# P4_CCD_CAM_BOARD_MCU.net
KiCad netlist of a schematic drawn in Altium Designer
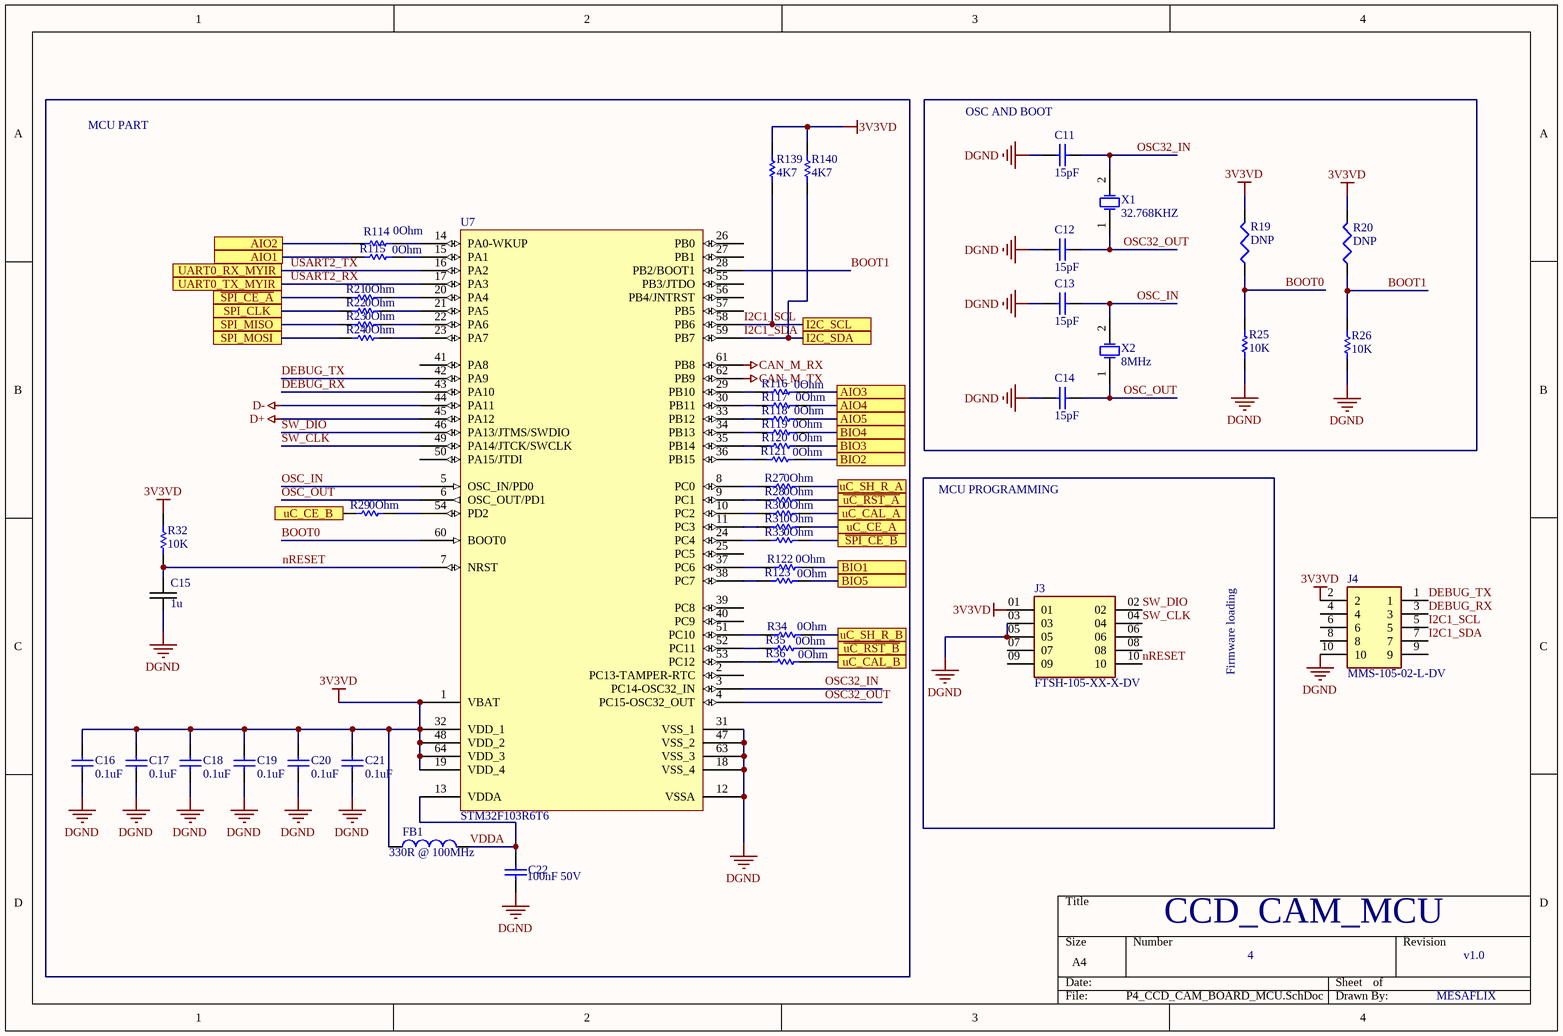
[diagram p0: P4_CCD_CAM_BOARD_MCU.SchDoc]

(export (version "E")
  (design (tool "Eeschema 10.0.6"))
  (components
    (comp (ref "C11")
      (value "15pF")
      (footprint "CAP0603")
      (description "CAP CER 15PF 50V C0G/NP0 0603")
      (libsource (lib "CAP_Library") (part "CAP0603_15pF"))
    )
    (comp (ref "C12")
      (value "15pF")
      (footprint "CAP0603")
      (description "CAP CER 15PF 50V C0G/NP0 0603")
      (libsource (lib "CAP_Library") (part "CAP0603_15pF"))
    )
    (comp (ref "C13")
      (value "15pF")
      (footprint "CAP0603")
      (description "CAP CER 15PF 50V C0G/NP0 0603")
      (libsource (lib "CAP_Library") (part "CAP0603_15pF"))
    )
    (comp (ref "C14")
      (value "15pF")
      (footprint "CAP0603")
      (description "CAP CER 15PF 50V C0G/NP0 0603")
      (libsource (lib "CAP_Library") (part "CAP0603_15pF"))
    )
    (comp (ref "C15")
      (value "1u")
      (footprint "C0603")
      (description "CAP CER 1UF 25V X7R 0603")
      (fields
        (field (name "MANUFACTURER PART NUMBER") "CL10B105KA8NNNC")
        (field (name "DIGIKEY PART NUMBER") "1276-1184-1-ND")
      )
      (libsource (lib "Database_Lib") (part "Capacitor"))
    )
    (comp (ref "C16")
      (value "0.1uF")
      (footprint "C 0402(1005)x0.5")
      (description "Capacitor")
      (fields
        (field (name "MANUFACTURER") "Murata")
        (field (name "MANUFACTURER PART NUMBER") "GRM155R71C104KA88D")
      )
      (libsource (lib "Miscellaneous Devices") (part "Cap"))
    )
    (comp (ref "C17")
      (value "0.1uF")
      (footprint "C 0402(1005)x0.5")
      (description "Capacitor")
      (fields
        (field (name "MANUFACTURER") "Murata")
        (field (name "MANUFACTURER PART NUMBER") "GRM155R71C104KA88D")
      )
      (libsource (lib "Miscellaneous Devices") (part "Cap"))
    )
    (comp (ref "C18")
      (value "0.1uF")
      (footprint "C 0402(1005)x0.5")
      (description "Capacitor")
      (fields
        (field (name "MANUFACTURER") "Murata")
        (field (name "MANUFACTURER PART NUMBER") "GRM155R71C104KA88D")
      )
      (libsource (lib "Miscellaneous Devices") (part "Cap"))
    )
    (comp (ref "C19")
      (value "0.1uF")
      (footprint "C 0402(1005)x0.5")
      (description "Capacitor")
      (fields
        (field (name "MANUFACTURER") "Murata")
        (field (name "MANUFACTURER PART NUMBER") "GRM155R71C104KA88D")
      )
      (libsource (lib "Miscellaneous Devices") (part "Cap"))
    )
    (comp (ref "C20")
      (value "0.1uF")
      (footprint "C 0402(1005)x0.5")
      (description "Capacitor")
      (fields
        (field (name "MANUFACTURER") "Murata")
        (field (name "MANUFACTURER PART NUMBER") "GRM155R71C104KA88D")
      )
      (libsource (lib "Miscellaneous Devices") (part "Cap"))
    )
    (comp (ref "C21")
      (value "0.1uF")
      (footprint "C 0402(1005)x0.5")
      (description "Capacitor")
      (fields
        (field (name "MANUFACTURER") "Murata")
        (field (name "MANUFACTURER PART NUMBER") "GRM155R71C104KA88D")
      )
      (libsource (lib "Miscellaneous Devices") (part "Cap"))
    )
    (comp (ref "C22")
      (value "100nF 50V")
      (footprint "CAP0603")
      (description "CAP CER 0.1UF 50V X7R 0603")
      (libsource (lib "CAP_Library") (part "CAP0603_100nF"))
    )
    (comp (ref "FB1")
      (value "330R @ 100MHz")
      (footprint "FB0603")
      (description "FERRITE BEAD 330 OHM 0603 1LN")
      (libsource (lib "FB_Library") (part "FB0603_330R@100MHz"))
    )
    (comp (ref "J3")
      (value "FTSH-105-XX-X-DV")
      (footprint "SAMTEC_FTSH-105-XX-X-DV")
      (description "Connector Header Surface Mount 10 position 0.050 (1.27mm)")
      (fields (field (name "MF") "Samtec") (field (name "MP") "FTSH-105-01-L-DV"))
      (libsource (lib "FTSH-105-XX-X-DV") (part "FTSH-105-XX-X-DV"))
    )
    (comp (ref "J4")
      (value "MMS-105-02-L-DV")
      (footprint "SAMTEC_MMS-105-02-L-DV")
      (description "10 Position Receptacle Connector Surface Mount")
      (fields (field (name "MF") "Samtec"))
      (libsource (lib "CCD_CAM_BOARD_1") (part "MMS-105-02-L-DV"))
    )
    (comp (ref "R19")
      (value "10k")
      (footprint "RES0603")
      (description "RES SMD 10K OHM 5% 1/10W 0603")
      (fields (field (name "ASSEMBLY") "DNP"))
      (libsource (lib "RES_Library") (part "RES0603_10k"))
    )
    (comp (ref "R20")
      (value "10k")
      (footprint "RES0603")
      (description "RES SMD 10K OHM 5% 1/10W 0603")
      (fields (field (name "ASSEMBLY") "DNP"))
      (libsource (lib "RES_Library") (part "RES0603_10k"))
    )
    (comp (ref "R21")
      (value "0Ohm")
      (footprint "R 0402(1005)")
      (fields
        (field (name "DIGIKEYPARTNUMBER") "311-0.0LDCT-ND")
        (field (name "MANUFACTURER") "Yageo")
        (field (name "MANUFACTURERPARTNUMBER") "AC0603FR-070RL")
      )
      (libsource (lib "TESLA_PCB_LIB") (part "RES_1K_0603"))
    )
    (comp (ref "R22")
      (value "0Ohm")
      (footprint "R 0402(1005)")
      (fields
        (field (name "DIGIKEYPARTNUMBER") "311-0.0LDCT-ND")
        (field (name "MANUFACTURER") "Yageo")
        (field (name "MANUFACTURERPARTNUMBER") "AC0603FR-070RL")
      )
      (libsource (lib "TESLA_PCB_LIB") (part "RES_1K_0603"))
    )
    (comp (ref "R23")
      (value "0Ohm")
      (footprint "R 0402(1005)")
      (fields
        (field (name "DIGIKEYPARTNUMBER") "311-0.0LDCT-ND")
        (field (name "MANUFACTURER") "Yageo")
        (field (name "MANUFACTURERPARTNUMBER") "AC0603FR-070RL")
      )
      (libsource (lib "TESLA_PCB_LIB") (part "RES_1K_0603"))
    )
    (comp (ref "R24")
      (value "0Ohm")
      (footprint "R 0402(1005)")
      (fields
        (field (name "DIGIKEYPARTNUMBER") "311-0.0LDCT-ND")
        (field (name "MANUFACTURER") "Yageo")
        (field (name "MANUFACTURERPARTNUMBER") "AC0603FR-070RL")
      )
      (libsource (lib "TESLA_PCB_LIB") (part "RES_1K_0603"))
    )
    (comp (ref "R25")
      (value "10K")
      (footprint "RES0603")
      (fields
        (field (name "DIGIKEYPARTNUMBER") "YAG2122CT-ND")
        (field (name "MANUFACTURER") "Yageo")
        (field (name "MANUFACTURERPARTNUMBER") "AT0603FRE0710KL")
      )
      (libsource (lib "TESLA_PCB_LIB") (part "RES_1K_0603"))
    )
    (comp (ref "R26")
      (value "10K")
      (footprint "RES0603")
      (fields
        (field (name "DIGIKEYPARTNUMBER") "YAG2122CT-ND")
        (field (name "MANUFACTURER") "Yageo")
        (field (name "MANUFACTURERPARTNUMBER") "AT0603FRE0710KL")
      )
      (libsource (lib "TESLA_PCB_LIB") (part "RES_1K_0603"))
    )
    (comp (ref "R27")
      (value "0Ohm")
      (footprint "R 0402(1005)")
      (fields
        (field (name "DIGIKEYPARTNUMBER") "311-0.0LDCT-ND")
        (field (name "MANUFACTURER") "Yageo")
        (field (name "MANUFACTURERPARTNUMBER") "AC0603FR-070RL")
      )
      (libsource (lib "TESLA_PCB_LIB") (part "RES_1K_0603"))
    )
    (comp (ref "R28")
      (value "0Ohm")
      (footprint "R 0402(1005)")
      (fields
        (field (name "DIGIKEYPARTNUMBER") "311-0.0LDCT-ND")
        (field (name "MANUFACTURER") "Yageo")
        (field (name "MANUFACTURERPARTNUMBER") "AC0603FR-070RL")
      )
      (libsource (lib "TESLA_PCB_LIB") (part "RES_1K_0603"))
    )
    (comp (ref "R29")
      (value "0Ohm")
      (footprint "R 0402(1005)")
      (fields
        (field (name "DIGIKEYPARTNUMBER") "311-0.0LDCT-ND")
        (field (name "MANUFACTURER") "Yageo")
        (field (name "MANUFACTURERPARTNUMBER") "AC0603FR-070RL")
      )
      (libsource (lib "TESLA_PCB_LIB") (part "RES_1K_0603"))
    )
    (comp (ref "R30")
      (value "0Ohm")
      (footprint "R 0402(1005)")
      (fields
        (field (name "DIGIKEYPARTNUMBER") "311-0.0LDCT-ND")
        (field (name "MANUFACTURER") "Yageo")
        (field (name "MANUFACTURERPARTNUMBER") "AC0603FR-070RL")
      )
      (libsource (lib "TESLA_PCB_LIB") (part "RES_1K_0603"))
    )
    (comp (ref "R31")
      (value "0Ohm")
      (footprint "R 0402(1005)")
      (fields
        (field (name "DIGIKEYPARTNUMBER") "311-0.0LDCT-ND")
        (field (name "MANUFACTURER") "Yageo")
        (field (name "MANUFACTURERPARTNUMBER") "AC0603FR-070RL")
      )
      (libsource (lib "TESLA_PCB_LIB") (part "RES_1K_0603"))
    )
    (comp (ref "R32")
      (value "10K")
      (footprint "RES0603")
      (fields
        (field (name "DIGIKEYPARTNUMBER") "YAG2122CT-ND")
        (field (name "MANUFACTURER") "Yageo")
        (field (name "MANUFACTURERPARTNUMBER") "AT0603FRE0710KL")
      )
      (libsource (lib "TESLA_PCB_LIB") (part "RES_1K_0603"))
    )
    (comp (ref "R33")
      (value "0Ohm")
      (footprint "R 0402(1005)")
      (fields
        (field (name "DIGIKEYPARTNUMBER") "311-0.0LDCT-ND")
        (field (name "MANUFACTURER") "Yageo")
        (field (name "MANUFACTURERPARTNUMBER") "AC0603FR-070RL")
      )
      (libsource (lib "TESLA_PCB_LIB") (part "RES_1K_0603"))
    )
    (comp (ref "R34")
      (value "0Ohm")
      (footprint "R 0402(1005)")
      (fields
        (field (name "DIGIKEYPARTNUMBER") "311-0.0LDCT-ND")
        (field (name "MANUFACTURER") "Yageo")
        (field (name "MANUFACTURERPARTNUMBER") "AC0603FR-070RL")
      )
      (libsource (lib "TESLA_PCB_LIB") (part "RES_1K_0603"))
    )
    (comp (ref "R35")
      (value "0Ohm")
      (footprint "R 0402(1005)")
      (fields
        (field (name "DIGIKEYPARTNUMBER") "311-0.0LDCT-ND")
        (field (name "MANUFACTURER") "Yageo")
        (field (name "MANUFACTURERPARTNUMBER") "AC0603FR-070RL")
      )
      (libsource (lib "TESLA_PCB_LIB") (part "RES_1K_0603"))
    )
    (comp (ref "R36")
      (value "0Ohm")
      (footprint "R 0402(1005)")
      (fields
        (field (name "DIGIKEYPARTNUMBER") "311-0.0LDCT-ND")
        (field (name "MANUFACTURER") "Yageo")
        (field (name "MANUFACTURERPARTNUMBER") "AC0603FR-070RL")
      )
      (libsource (lib "TESLA_PCB_LIB") (part "RES_1K_0603"))
    )
    (comp (ref "R114")
      (value "0Ohm")
      (footprint "R 0402(1005)")
      (fields
        (field (name "DIGIKEYPARTNUMBER") "311-0.0LDCT-ND")
        (field (name "MANUFACTURER") "Yageo")
        (field (name "MANUFACTURERPARTNUMBER") "AC0603FR-070RL")
      )
      (libsource (lib "TESLA_PCB_LIB") (part "RES_1K_0603"))
    )
    (comp (ref "R115")
      (value "0Ohm")
      (footprint "R 0402(1005)")
      (fields
        (field (name "DIGIKEYPARTNUMBER") "311-0.0LDCT-ND")
        (field (name "MANUFACTURER") "Yageo")
        (field (name "MANUFACTURERPARTNUMBER") "AC0603FR-070RL")
      )
      (libsource (lib "TESLA_PCB_LIB") (part "RES_1K_0603"))
    )
    (comp (ref "R116")
      (value "0Ohm")
      (footprint "R 0402(1005)")
      (fields
        (field (name "DIGIKEYPARTNUMBER") "311-0.0LDCT-ND")
        (field (name "MANUFACTURER") "Yageo")
        (field (name "MANUFACTURERPARTNUMBER") "AC0603FR-070RL")
      )
      (libsource (lib "TESLA_PCB_LIB") (part "RES_1K_0603"))
    )
    (comp (ref "R117")
      (value "0Ohm")
      (footprint "R 0402(1005)")
      (fields
        (field (name "DIGIKEYPARTNUMBER") "311-0.0LDCT-ND")
        (field (name "MANUFACTURER") "Yageo")
        (field (name "MANUFACTURERPARTNUMBER") "AC0603FR-070RL")
      )
      (libsource (lib "TESLA_PCB_LIB") (part "RES_1K_0603"))
    )
    (comp (ref "R118")
      (value "0Ohm")
      (footprint "R 0402(1005)")
      (fields
        (field (name "DIGIKEYPARTNUMBER") "311-0.0LDCT-ND")
        (field (name "MANUFACTURER") "Yageo")
        (field (name "MANUFACTURERPARTNUMBER") "AC0603FR-070RL")
      )
      (libsource (lib "TESLA_PCB_LIB") (part "RES_1K_0603"))
    )
    (comp (ref "R119")
      (value "0Ohm")
      (footprint "R 0402(1005)")
      (fields
        (field (name "DIGIKEYPARTNUMBER") "311-0.0LDCT-ND")
        (field (name "MANUFACTURER") "Yageo")
        (field (name "MANUFACTURERPARTNUMBER") "AC0603FR-070RL")
      )
      (libsource (lib "TESLA_PCB_LIB") (part "RES_1K_0603"))
    )
    (comp (ref "R120")
      (value "0Ohm")
      (footprint "R 0402(1005)")
      (fields
        (field (name "DIGIKEYPARTNUMBER") "311-0.0LDCT-ND")
        (field (name "MANUFACTURER") "Yageo")
        (field (name "MANUFACTURERPARTNUMBER") "AC0603FR-070RL")
      )
      (libsource (lib "TESLA_PCB_LIB") (part "RES_1K_0603"))
    )
    (comp (ref "R121")
      (value "0Ohm")
      (footprint "R 0402(1005)")
      (fields
        (field (name "DIGIKEYPARTNUMBER") "311-0.0LDCT-ND")
        (field (name "MANUFACTURER") "Yageo")
        (field (name "MANUFACTURERPARTNUMBER") "AC0603FR-070RL")
      )
      (libsource (lib "TESLA_PCB_LIB") (part "RES_1K_0603"))
    )
    (comp (ref "R122")
      (value "0Ohm")
      (footprint "R 0402(1005)")
      (fields
        (field (name "DIGIKEYPARTNUMBER") "311-0.0LDCT-ND")
        (field (name "MANUFACTURER") "Yageo")
        (field (name "MANUFACTURERPARTNUMBER") "AC0603FR-070RL")
      )
      (libsource (lib "TESLA_PCB_LIB") (part "RES_1K_0603"))
    )
    (comp (ref "R123")
      (value "0Ohm")
      (footprint "R 0402(1005)")
      (fields
        (field (name "DIGIKEYPARTNUMBER") "311-0.0LDCT-ND")
        (field (name "MANUFACTURER") "Yageo")
        (field (name "MANUFACTURERPARTNUMBER") "AC0603FR-070RL")
      )
      (libsource (lib "TESLA_PCB_LIB") (part "RES_1K_0603"))
    )
    (comp (ref "R139")
      (value "4K7")
      (footprint "CAP_RES_1608_0603")
      (fields
        (field (name "DIGIKEYPARTNUMBER") "YAG3676CT-ND")
        (field (name "MANUFACTURER") "Yageo")
        (field (name "MANUFACTURERPARTNUMBER") "AC0603JR-074K7L")
      )
      (libsource (lib "TESLA_PCB_LIB") (part "RES_1K_0603"))
    )
    (comp (ref "R140")
      (value "4K7")
      (footprint "CAP_RES_1608_0603")
      (fields
        (field (name "DIGIKEYPARTNUMBER") "YAG3676CT-ND")
        (field (name "MANUFACTURER") "Yageo")
        (field (name "MANUFACTURERPARTNUMBER") "AC0603JR-074K7L")
      )
      (libsource (lib "TESLA_PCB_LIB") (part "RES_1K_0603"))
    )
    (comp (ref "U7")
      (value "STM32F103R6T6")
      (footprint "LQFP64_N")
      (description "STM32 ARM-based 32-bit MCU with 32 Kbytes Flash, 64-pin LQFP, Industrial Temperature")
      (fields (field (name "PUBLISHER") "Altium Limited"))
      (libsource (lib "ST Microcontroller 32-Bit STM32") (part "STM32F103R6T6"))
    )
    (comp (ref "X1")
      (value "32.768KHZ")
      (footprint "CRY_ABS07")
      (description "CRYSTAL 32.768KHZ 12.5PF SMD")
      (libsource (lib "MISC_Library") (part "CRY_32.768KHZ"))
    )
    (comp (ref "X2")
      (value "8MHz")
      (footprint "CRY_NX8045GB")
      (description "CRYSTAL 8.0000MHZ 8PF SMD")
      (libsource (lib "MISC_Library") (part "CRY_NX8045GB-8.000M-STD-CSJ-1"))
    )
  )
  (nets
    (net (code "1") (name "/AIO1") (class "Default")
      (node (ref "R115") (pin "2") (pinfunction "2_2") (pintype "passive"))
    )
    (net (code "2") (name "/AIO2") (class "Default")
      (node (ref "R114") (pin "2") (pinfunction "2_2") (pintype "passive"))
    )
    (net (code "3") (name "/AIO3") (class "Default")
      (node (ref "R116") (pin "2") (pinfunction "2_2") (pintype "passive"))
    )
    (net (code "4") (name "/AIO4") (class "Default")
      (node (ref "R117") (pin "2") (pinfunction "2_2") (pintype "passive"))
    )
    (net (code "5") (name "/AIO5") (class "Default")
      (node (ref "R118") (pin "2") (pinfunction "2_2") (pintype "passive"))
    )
    (net (code "6") (name "/BIO1") (class "Default")
      (node (ref "R122") (pin "2") (pinfunction "2_2") (pintype "passive"))
    )
    (net (code "7") (name "/BIO2") (class "Default")
      (node (ref "R121") (pin "2") (pinfunction "2_2") (pintype "passive"))
    )
    (net (code "8") (name "/BIO3") (class "Default")
      (node (ref "R120") (pin "2") (pinfunction "2_2") (pintype "passive"))
    )
    (net (code "9") (name "/BIO4") (class "Default")
      (node (ref "R119") (pin "2") (pinfunction "2_2") (pintype "passive"))
    )
    (net (code "10") (name "/BIO5") (class "Default")
      (node (ref "R123") (pin "2") (pinfunction "2_2") (pintype "passive"))
    )
    (net (code "11") (name "/BOOT0") (class "Default")
      (node (ref "R19") (pin "1") (pinfunction "1_1") (pintype "passive"))
      (node (ref "R25") (pin "1") (pinfunction "1_1") (pintype "passive"))
      (node (ref "U7") (pin "60") (pinfunction "BOOT0_60") (pintype "input"))
    )
    (net (code "12") (name "/BOOT1") (class "Default")
      (node (ref "R20") (pin "1") (pinfunction "1_1") (pintype "passive"))
      (node (ref "R26") (pin "1") (pinfunction "1_1") (pintype "passive"))
      (node (ref "U7") (pin "28") (pinfunction "PB2/BOOT1_28") (pintype "bidirectional"))
    )
    (net (code "13") (name "/DEBUG_RX") (class "Default")
      (node (ref "J4") (pin "3") (pinfunction "3_3") (pintype "passive"))
      (node (ref "U7") (pin "43") (pinfunction "PA10_43") (pintype "bidirectional"))
    )
    (net (code "14") (name "/DEBUG_TX") (class "Default")
      (node (ref "J4") (pin "1") (pinfunction "1_1") (pintype "passive"))
      (node (ref "U7") (pin "42") (pinfunction "PA9_42") (pintype "bidirectional"))
    )
    (net (code "15") (name "/I2C1_SCL") (class "Default")
      (node (ref "J4") (pin "5") (pinfunction "5_5") (pintype "passive"))
      (node (ref "R139") (pin "2") (pinfunction "2_2") (pintype "passive"))
      (node (ref "U7") (pin "58") (pinfunction "PB6_58") (pintype "bidirectional"))
    )
    (net (code "16") (name "/I2C1_SDA") (class "Default")
      (node (ref "J4") (pin "7") (pinfunction "7_7") (pintype "passive"))
      (node (ref "R140") (pin "2") (pinfunction "2_2") (pintype "passive"))
      (node (ref "U7") (pin "59") (pinfunction "PB7_59") (pintype "bidirectional"))
    )
    (net (code "17") (name "/OSC32_IN") (class "Default")
      (node (ref "C11") (pin "2") (pinfunction "2_2") (pintype "passive"))
      (node (ref "U7") (pin "3") (pinfunction "PC14-OSC32_IN_3") (pintype "bidirectional"))
      (node (ref "X1") (pin "2") (pinfunction "OSC2_2") (pintype "passive"))
    )
    (net (code "18") (name "/OSC32_OUT") (class "Default")
      (node (ref "C12") (pin "2") (pinfunction "2_2") (pintype "passive"))
      (node (ref "U7") (pin "4") (pinfunction "PC15-OSC32_OUT_4") (pintype "bidirectional"))
      (node (ref "X1") (pin "1") (pinfunction "OSC1_1") (pintype "passive"))
    )
    (net (code "19") (name "/OSC_IN") (class "Default")
      (node (ref "C13") (pin "2") (pinfunction "2_2") (pintype "passive"))
      (node (ref "U7") (pin "5") (pinfunction "OSC_IN/PD0_5") (pintype "input"))
      (node (ref "X2") (pin "2") (pinfunction "OSC2_2") (pintype "passive"))
    )
    (net (code "20") (name "/OSC_OUT") (class "Default")
      (node (ref "C14") (pin "2") (pinfunction "2_2") (pintype "passive"))
      (node (ref "U7") (pin "6") (pinfunction "OSC_OUT/PD1_6") (pintype "output"))
      (node (ref "X2") (pin "1") (pinfunction "OSC1_1") (pintype "passive"))
    )
    (net (code "21") (name "/SPI_CLK") (class "Default")
      (node (ref "R22") (pin "1") (pinfunction "1_1") (pintype "passive"))
    )
    (net (code "22") (name "/SPI_MISO") (class "Default")
      (node (ref "R23") (pin "1") (pinfunction "1_1") (pintype "passive"))
    )
    (net (code "23") (name "/SPI_MOSI") (class "Default")
      (node (ref "R24") (pin "1") (pinfunction "1_1") (pintype "passive"))
    )
    (net (code "24") (name "/SW_CLK") (class "Default")
      (node (ref "J3") (pin "04") (pinfunction "04_04") (pintype "passive"))
      (node (ref "U7") (pin "49") (pinfunction "PA14/JTCK/SWCLK_49") (pintype "bidirectional"))
    )
    (net (code "25") (name "/SW_DIO") (class "Default")
      (node (ref "J3") (pin "02") (pinfunction "02_02") (pintype "passive"))
      (node (ref "U7") (pin "46") (pinfunction "PA13/JTMS/SWDIO_46") (pintype "bidirectional"))
    )
    (net (code "26") (name "/USART2_RX") (class "Default")
      (node (ref "U7") (pin "17") (pinfunction "PA3_17") (pintype "bidirectional"))
    )
    (net (code "27") (name "/USART2_TX") (class "Default")
      (node (ref "U7") (pin "16") (pinfunction "PA2_16") (pintype "bidirectional"))
    )
    (net (code "28") (name "/VDDA") (class "Default")
      (node (ref "C22") (pin "2") (pinfunction "2_2") (pintype "passive"))
      (node (ref "FB1") (pin "2") (pinfunction "2_2") (pintype "passive"))
      (node (ref "U7") (pin "13") (pinfunction "VDDA_13") (pintype "power_in"))
    )
    (net (code "29") (name "/nRESET") (class "Default")
      (node (ref "C15") (pin "1") (pinfunction "1_1") (pintype "passive"))
      (node (ref "J3") (pin "10") (pinfunction "10_10") (pintype "passive"))
      (node (ref "R32") (pin "2") (pinfunction "2_2") (pintype "passive"))
      (node (ref "U7") (pin "7") (pinfunction "NRST_7") (pintype "bidirectional"))
    )
    (net (code "30") (name "/uC_CAL_A") (class "Default")
      (node (ref "R30") (pin "2") (pinfunction "2_2") (pintype "passive"))
    )
    (net (code "31") (name "/uC_CAL_B") (class "Default")
      (node (ref "R36") (pin "2") (pinfunction "2_2") (pintype "passive"))
    )
    (net (code "32") (name "/uC_CE_A") (class "Default")
      (node (ref "R31") (pin "2") (pinfunction "2_2") (pintype "passive"))
    )
    (net (code "33") (name "/uC_CE_B") (class "Default")
      (node (ref "R29") (pin "1") (pinfunction "1_1") (pintype "passive"))
    )
    (net (code "34") (name "/uC_SH_R_A") (class "Default")
      (node (ref "R27") (pin "2") (pinfunction "2_2") (pintype "passive"))
    )
    (net (code "35") (name "/uC_SH_R_B") (class "Default")
      (node (ref "R34") (pin "2") (pinfunction "2_2") (pintype "passive"))
    )
    (net (code "36") (name "/~{SPI_CE_A}") (class "Default")
      (node (ref "R21") (pin "1") (pinfunction "1_1") (pintype "passive"))
    )
    (net (code "37") (name "/~{SPI_CE_B}") (class "Default")
      (node (ref "R33") (pin "2") (pinfunction "2_2") (pintype "passive"))
    )
    (net (code "38") (name "/~{uC_RST_A}") (class "Default")
      (node (ref "R28") (pin "2") (pinfunction "2_2") (pintype "passive"))
    )
    (net (code "39") (name "/~{uC_RST_B}") (class "Default")
      (node (ref "R35") (pin "2") (pinfunction "2_2") (pintype "passive"))
    )
    (net (code "40") (name "3V3VD") (class "Default")
      (node (ref "C16") (pin "2") (pinfunction "2_2") (pintype "passive"))
      (node (ref "C17") (pin "2") (pinfunction "2_2") (pintype "passive"))
      (node (ref "C18") (pin "2") (pinfunction "2_2") (pintype "passive"))
      (node (ref "C19") (pin "2") (pinfunction "2_2") (pintype "passive"))
      (node (ref "C20") (pin "2") (pinfunction "2_2") (pintype "passive"))
      (node (ref "C21") (pin "2") (pinfunction "2_2") (pintype "passive"))
      (node (ref "FB1") (pin "1") (pinfunction "1_1") (pintype "passive"))
      (node (ref "J3") (pin "01") (pinfunction "01_01") (pintype "passive"))
      (node (ref "J4") (pin "2") (pinfunction "2_2") (pintype "passive"))
      (node (ref "R139") (pin "1") (pinfunction "1_1") (pintype "passive"))
      (node (ref "R140") (pin "1") (pinfunction "1_1") (pintype "passive"))
      (node (ref "R19") (pin "2") (pinfunction "2_2") (pintype "passive"))
      (node (ref "R20") (pin "2") (pinfunction "2_2") (pintype "passive"))
      (node (ref "R32") (pin "1") (pinfunction "1_1") (pintype "passive"))
      (node (ref "U7") (pin "1") (pinfunction "VBAT_1") (pintype "power_in"))
      (node (ref "U7") (pin "19") (pinfunction "VDD_4_19") (pintype "power_in"))
      (node (ref "U7") (pin "32") (pinfunction "VDD_1_32") (pintype "power_in"))
      (node (ref "U7") (pin "48") (pinfunction "VDD_2_48") (pintype "power_in"))
      (node (ref "U7") (pin "64") (pinfunction "VDD_3_64") (pintype "power_in"))
    )
    (net (code "41") (name "CAN_M_RX") (class "Default")
      (node (ref "U7") (pin "61") (pinfunction "PB8_61") (pintype "bidirectional"))
    )
    (net (code "42") (name "CAN_M_TX") (class "Default")
      (node (ref "U7") (pin "62") (pinfunction "PB9_62") (pintype "bidirectional"))
    )
    (net (code "43") (name "D+") (class "Default")
      (node (ref "U7") (pin "45") (pinfunction "PA12_45") (pintype "bidirectional"))
    )
    (net (code "44") (name "D-") (class "Default")
      (node (ref "U7") (pin "44") (pinfunction "PA11_44") (pintype "bidirectional"))
    )
    (net (code "45") (name "DGND") (class "Default")
      (node (ref "C11") (pin "1") (pinfunction "1_1") (pintype "passive"))
      (node (ref "C12") (pin "1") (pinfunction "1_1") (pintype "passive"))
      (node (ref "C13") (pin "1") (pinfunction "1_1") (pintype "passive"))
      (node (ref "C14") (pin "1") (pinfunction "1_1") (pintype "passive"))
      (node (ref "C15") (pin "2") (pinfunction "2_2") (pintype "passive"))
      (node (ref "C16") (pin "1") (pinfunction "1_1") (pintype "passive"))
      (node (ref "C17") (pin "1") (pinfunction "1_1") (pintype "passive"))
      (node (ref "C18") (pin "1") (pinfunction "1_1") (pintype "passive"))
      (node (ref "C19") (pin "1") (pinfunction "1_1") (pintype "passive"))
      (node (ref "C20") (pin "1") (pinfunction "1_1") (pintype "passive"))
      (node (ref "C21") (pin "1") (pinfunction "1_1") (pintype "passive"))
      (node (ref "C22") (pin "1") (pinfunction "1_1") (pintype "passive"))
      (node (ref "J3") (pin "03") (pinfunction "03_03") (pintype "passive"))
      (node (ref "J3") (pin "05") (pinfunction "05_05") (pintype "passive"))
      (node (ref "J4") (pin "10") (pinfunction "10_10") (pintype "passive"))
      (node (ref "R25") (pin "2") (pinfunction "2_2") (pintype "passive"))
      (node (ref "R26") (pin "2") (pinfunction "2_2") (pintype "passive"))
      (node (ref "U7") (pin "12") (pinfunction "VSSA_12") (pintype "power_in"))
      (node (ref "U7") (pin "18") (pinfunction "VSS_4_18") (pintype "power_in"))
      (node (ref "U7") (pin "31") (pinfunction "VSS_1_31") (pintype "power_in"))
      (node (ref "U7") (pin "47") (pinfunction "VSS_2_47") (pintype "power_in"))
      (node (ref "U7") (pin "63") (pinfunction "VSS_3_63") (pintype "power_in"))
    )
    (net (code "46") (name "Net-(U7-PA0-WKUP)") (class "Default")
      (node (ref "R114") (pin "1") (pinfunction "1_1") (pintype "passive"))
      (node (ref "U7") (pin "14") (pinfunction "PA0-WKUP_14") (pintype "bidirectional"))
    )
    (net (code "47") (name "Net-(U7-PA1)") (class "Default")
      (node (ref "R115") (pin "1") (pinfunction "1_1") (pintype "passive"))
      (node (ref "U7") (pin "15") (pinfunction "PA1_15") (pintype "bidirectional"))
    )
    (net (code "48") (name "Net-(U7-PA4)") (class "Default")
      (node (ref "R21") (pin "2") (pinfunction "2_2") (pintype "passive"))
      (node (ref "U7") (pin "20") (pinfunction "PA4_20") (pintype "bidirectional"))
    )
    (net (code "49") (name "Net-(U7-PA5)") (class "Default")
      (node (ref "R22") (pin "2") (pinfunction "2_2") (pintype "passive"))
      (node (ref "U7") (pin "21") (pinfunction "PA5_21") (pintype "bidirectional"))
    )
    (net (code "50") (name "Net-(U7-PA6)") (class "Default")
      (node (ref "R23") (pin "2") (pinfunction "2_2") (pintype "passive"))
      (node (ref "U7") (pin "22") (pinfunction "PA6_22") (pintype "bidirectional"))
    )
    (net (code "51") (name "Net-(U7-PA7)") (class "Default")
      (node (ref "R24") (pin "2") (pinfunction "2_2") (pintype "passive"))
      (node (ref "U7") (pin "23") (pinfunction "PA7_23") (pintype "bidirectional"))
    )
    (net (code "52") (name "Net-(U7-PB10)") (class "Default")
      (node (ref "R116") (pin "1") (pinfunction "1_1") (pintype "passive"))
      (node (ref "U7") (pin "29") (pinfunction "PB10_29") (pintype "bidirectional"))
    )
    (net (code "53") (name "Net-(U7-PB11)") (class "Default")
      (node (ref "R117") (pin "1") (pinfunction "1_1") (pintype "passive"))
      (node (ref "U7") (pin "30") (pinfunction "PB11_30") (pintype "bidirectional"))
    )
    (net (code "54") (name "Net-(U7-PB12)") (class "Default")
      (node (ref "R118") (pin "1") (pinfunction "1_1") (pintype "passive"))
      (node (ref "U7") (pin "33") (pinfunction "PB12_33") (pintype "bidirectional"))
    )
    (net (code "55") (name "Net-(U7-PB13)") (class "Default")
      (node (ref "R119") (pin "1") (pinfunction "1_1") (pintype "passive"))
      (node (ref "U7") (pin "34") (pinfunction "PB13_34") (pintype "bidirectional"))
    )
    (net (code "56") (name "Net-(U7-PB14)") (class "Default")
      (node (ref "R120") (pin "1") (pinfunction "1_1") (pintype "passive"))
      (node (ref "U7") (pin "35") (pinfunction "PB14_35") (pintype "bidirectional"))
    )
    (net (code "57") (name "Net-(U7-PB15)") (class "Default")
      (node (ref "R121") (pin "1") (pinfunction "1_1") (pintype "passive"))
      (node (ref "U7") (pin "36") (pinfunction "PB15_36") (pintype "bidirectional"))
    )
    (net (code "58") (name "Net-(U7-PC0)") (class "Default")
      (node (ref "R27") (pin "1") (pinfunction "1_1") (pintype "passive"))
      (node (ref "U7") (pin "8") (pinfunction "PC0_8") (pintype "bidirectional"))
    )
    (net (code "59") (name "Net-(U7-PC1)") (class "Default")
      (node (ref "R28") (pin "1") (pinfunction "1_1") (pintype "passive"))
      (node (ref "U7") (pin "9") (pinfunction "PC1_9") (pintype "bidirectional"))
    )
    (net (code "60") (name "Net-(U7-PC2)") (class "Default")
      (node (ref "R30") (pin "1") (pinfunction "1_1") (pintype "passive"))
      (node (ref "U7") (pin "10") (pinfunction "PC2_10") (pintype "bidirectional"))
    )
    (net (code "61") (name "Net-(U7-PC3)") (class "Default")
      (node (ref "R31") (pin "1") (pinfunction "1_1") (pintype "passive"))
      (node (ref "U7") (pin "11") (pinfunction "PC3_11") (pintype "bidirectional"))
    )
    (net (code "62") (name "Net-(U7-PC4)") (class "Default")
      (node (ref "R33") (pin "1") (pinfunction "1_1") (pintype "passive"))
      (node (ref "U7") (pin "24") (pinfunction "PC4_24") (pintype "bidirectional"))
    )
    (net (code "63") (name "Net-(U7-PC6)") (class "Default")
      (node (ref "R122") (pin "1") (pinfunction "1_1") (pintype "passive"))
      (node (ref "U7") (pin "37") (pinfunction "PC6_37") (pintype "bidirectional"))
    )
    (net (code "64") (name "Net-(U7-PC7)") (class "Default")
      (node (ref "R123") (pin "1") (pinfunction "1_1") (pintype "passive"))
      (node (ref "U7") (pin "38") (pinfunction "PC7_38") (pintype "bidirectional"))
    )
    (net (code "65") (name "Net-(U7-PC10)") (class "Default")
      (node (ref "R34") (pin "1") (pinfunction "1_1") (pintype "passive"))
      (node (ref "U7") (pin "51") (pinfunction "PC10_51") (pintype "bidirectional"))
    )
    (net (code "66") (name "Net-(U7-PC11)") (class "Default")
      (node (ref "R35") (pin "1") (pinfunction "1_1") (pintype "passive"))
      (node (ref "U7") (pin "52") (pinfunction "PC11_52") (pintype "bidirectional"))
    )
    (net (code "67") (name "Net-(U7-PC12)") (class "Default")
      (node (ref "R36") (pin "1") (pinfunction "1_1") (pintype "passive"))
      (node (ref "U7") (pin "53") (pinfunction "PC12_53") (pintype "bidirectional"))
    )
    (net (code "68") (name "Net-(U7-PD2)") (class "Default")
      (node (ref "R29") (pin "2") (pinfunction "2_2") (pintype "passive"))
      (node (ref "U7") (pin "54") (pinfunction "PD2_54") (pintype "bidirectional"))
    )
    (net (code "69") (name "unconnected-(J3-Pad06)") (class "Default")
      (node (ref "J3") (pin "06") (pinfunction "06_06") (pintype "passive"))
    )
    (net (code "70") (name "unconnected-(J3-Pad07)") (class "Default")
      (node (ref "J3") (pin "07") (pinfunction "07_07") (pintype "passive"))
    )
    (net (code "71") (name "unconnected-(J3-Pad08)") (class "Default")
      (node (ref "J3") (pin "08") (pinfunction "08_08") (pintype "passive"))
    )
    (net (code "72") (name "unconnected-(J3-Pad09)") (class "Default")
      (node (ref "J3") (pin "09") (pinfunction "09_09") (pintype "passive"))
    )
    (net (code "73") (name "unconnected-(J4-Pad4)") (class "Default")
      (node (ref "J4") (pin "4") (pinfunction "4_4") (pintype "passive"))
    )
    (net (code "74") (name "unconnected-(J4-Pad6)") (class "Default")
      (node (ref "J4") (pin "6") (pinfunction "6_6") (pintype "passive"))
    )
    (net (code "75") (name "unconnected-(J4-Pad8)") (class "Default")
      (node (ref "J4") (pin "8") (pinfunction "8_8") (pintype "passive"))
    )
    (net (code "76") (name "unconnected-(J4-Pad9)") (class "Default")
      (node (ref "J4") (pin "9") (pinfunction "9_9") (pintype "passive"))
    )
    (net (code "77") (name "unconnected-(U7-PA8-Pad41)") (class "Default")
      (node (ref "U7") (pin "41") (pinfunction "PA8_41") (pintype "bidirectional"))
    )
    (net (code "78") (name "unconnected-(U7-PA15{slash}JTDI-Pad50)") (class "Default")
      (node (ref "U7") (pin "50") (pinfunction "PA15/JTDI_50") (pintype "bidirectional"))
    )
    (net (code "79") (name "unconnected-(U7-PB0-Pad26)") (class "Default")
      (node (ref "U7") (pin "26") (pinfunction "PB0_26") (pintype "bidirectional"))
    )
    (net (code "80") (name "unconnected-(U7-PB1-Pad27)") (class "Default")
      (node (ref "U7") (pin "27") (pinfunction "PB1_27") (pintype "bidirectional"))
    )
    (net (code "81") (name "unconnected-(U7-PB3{slash}JTDO-Pad55)") (class "Default")
      (node (ref "U7") (pin "55") (pinfunction "PB3/JTDO_55") (pintype "bidirectional"))
    )
    (net (code "82") (name "unconnected-(U7-PB4{slash}JNTRST-Pad56)") (class "Default")
      (node (ref "U7") (pin "56") (pinfunction "PB4/JNTRST_56") (pintype "bidirectional"))
    )
    (net (code "83") (name "unconnected-(U7-PB5-Pad57)") (class "Default")
      (node (ref "U7") (pin "57") (pinfunction "PB5_57") (pintype "bidirectional"))
    )
    (net (code "84") (name "unconnected-(U7-PC5-Pad25)") (class "Default")
      (node (ref "U7") (pin "25") (pinfunction "PC5_25") (pintype "bidirectional"))
    )
    (net (code "85") (name "unconnected-(U7-PC8-Pad39)") (class "Default")
      (node (ref "U7") (pin "39") (pinfunction "PC8_39") (pintype "bidirectional"))
    )
    (net (code "86") (name "unconnected-(U7-PC9-Pad40)") (class "Default")
      (node (ref "U7") (pin "40") (pinfunction "PC9_40") (pintype "bidirectional"))
    )
    (net (code "87") (name "unconnected-(U7-PC13-TAMPER-RTC-Pad2)") (class "Default")
      (node (ref "U7") (pin "2") (pinfunction "PC13-TAMPER-RTC_2") (pintype "bidirectional"))
    )
  )
)
